# pcb1a.net
KiCad netlist of a schematic drawn in EAGLE
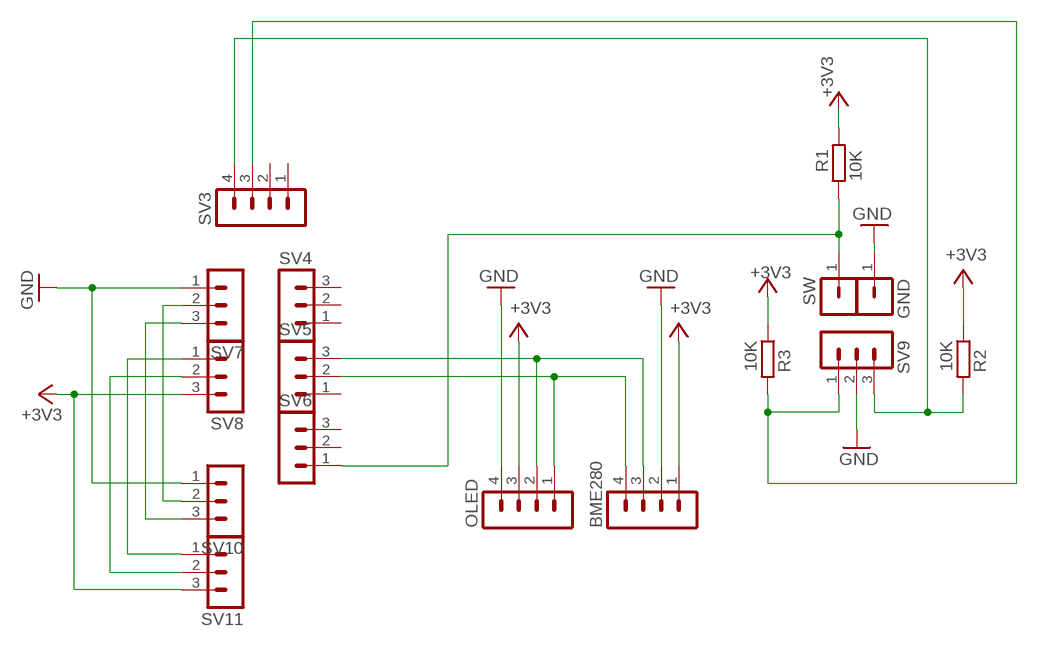
[diagram p0: schematic, sheet 1]

(export (version "E")
  (design (tool "Eeschema 10.0.6"))
  (components
    (comp (ref "BME280")
      (value "PINHEAD-MA04-1")
      (footprint "eagle-import:PINHEAD-MA04-1")
      (libsource (lib "eagle-import") (part "PINHEAD-MA04-1"))
    )
    (comp (ref "GND")
      (value "PINHEAD-MA01-1")
      (footprint "eagle-import:PINHEAD-MA01-1")
      (libsource (lib "eagle-import") (part "PINHEAD-MA01-1"))
    )
    (comp (ref "OLED")
      (value "PINHEAD-MA04-1")
      (footprint "eagle-import:PINHEAD-MA04-1")
      (libsource (lib "eagle-import") (part "PINHEAD-MA04-1"))
    )
    (comp (ref "R1")
      (value "10K")
      (footprint "eagle-import:0204_5")
      (libsource (lib "eagle-import") (part "R-EU_0204/5"))
    )
    (comp (ref "R2")
      (value "10K")
      (footprint "eagle-import:0204_5")
      (libsource (lib "eagle-import") (part "R-EU_0204/5"))
    )
    (comp (ref "R3")
      (value "10K")
      (footprint "eagle-import:0204_5")
      (libsource (lib "eagle-import") (part "R-EU_0204/5"))
    )
    (comp (ref "SV3")
      (value "PINHEAD-MA04-1")
      (footprint "eagle-import:PINHEAD-MA04-1")
      (libsource (lib "eagle-import") (part "PINHEAD-MA04-1"))
    )
    (comp (ref "SV4")
      (value "PINHEAD-MA03-1")
      (footprint "eagle-import:PINHEAD-MA03-1")
      (libsource (lib "eagle-import") (part "PINHEAD-MA03-1"))
    )
    (comp (ref "SV5")
      (value "PINHEAD-MA03-1")
      (footprint "eagle-import:PINHEAD-MA03-1")
      (libsource (lib "eagle-import") (part "PINHEAD-MA03-1"))
    )
    (comp (ref "SV6")
      (value "PINHEAD-MA03-1")
      (footprint "eagle-import:PINHEAD-MA03-1")
      (libsource (lib "eagle-import") (part "PINHEAD-MA03-1"))
    )
    (comp (ref "SV7")
      (value "PINHEAD-MA03-1")
      (footprint "eagle-import:PINHEAD-MA03-1")
      (libsource (lib "eagle-import") (part "PINHEAD-MA03-1"))
    )
    (comp (ref "SV8")
      (value "PINHEAD-MA03-1")
      (footprint "eagle-import:PINHEAD-MA03-1")
      (libsource (lib "eagle-import") (part "PINHEAD-MA03-1"))
    )
    (comp (ref "SV9")
      (value "PINHEAD-MA03-1")
      (footprint "eagle-import:PINHEAD-MA03-1")
      (libsource (lib "eagle-import") (part "PINHEAD-MA03-1"))
    )
    (comp (ref "SV10")
      (value "PINHEAD-MA03-1")
      (footprint "eagle-import:PINHEAD-MA03-1")
      (libsource (lib "eagle-import") (part "PINHEAD-MA03-1"))
    )
    (comp (ref "SV11")
      (value "PINHEAD-MA03-1")
      (footprint "eagle-import:PINHEAD-MA03-1")
      (libsource (lib "eagle-import") (part "PINHEAD-MA03-1"))
    )
    (comp (ref "SW")
      (value "PINHEAD-MA01-1")
      (footprint "eagle-import:PINHEAD-MA01-1")
      (libsource (lib "eagle-import") (part "PINHEAD-MA01-1"))
    )
  )
  (nets
    (net (code "1") (name "+3V3") (class "Default")
      (node (ref "BME280") (pin "1") (pinfunction "1_1") (pintype "passive"))
      (node (ref "OLED") (pin "3") (pinfunction "3_3") (pintype "passive"))
      (node (ref "R1") (pin "2") (pinfunction "2_2") (pintype "passive"))
      (node (ref "R2") (pin "1") (pinfunction "1_1") (pintype "passive"))
      (node (ref "R3") (pin "1") (pinfunction "1_1") (pintype "passive"))
      (node (ref "SV11") (pin "3") (pinfunction "3_3") (pintype "passive"))
      (node (ref "SV8") (pin "3") (pinfunction "3_3") (pintype "passive"))
    )
    (net (code "2") (name "GND") (class "Default")
      (node (ref "BME280") (pin "2") (pinfunction "2_2") (pintype "passive"))
      (node (ref "GND") (pin "1") (pinfunction "1_1") (pintype "passive"))
      (node (ref "OLED") (pin "4") (pinfunction "4_4") (pintype "passive"))
      (node (ref "SV10") (pin "1") (pinfunction "1_1") (pintype "passive"))
      (node (ref "SV7") (pin "1") (pinfunction "1_1") (pintype "passive"))
      (node (ref "SV9") (pin "2") (pinfunction "2_2") (pintype "passive"))
    )
    (net (code "3") (name "Net-(BME280-Pad3)") (class "Default")
      (node (ref "BME280") (pin "3") (pinfunction "3_3") (pintype "passive"))
      (node (ref "OLED") (pin "2") (pinfunction "2_2") (pintype "passive"))
      (node (ref "SV5") (pin "3") (pinfunction "3_3") (pintype "passive"))
    )
    (net (code "4") (name "Net-(BME280-Pad4)") (class "Default")
      (node (ref "BME280") (pin "4") (pinfunction "4_4") (pintype "passive"))
      (node (ref "OLED") (pin "1") (pinfunction "1_1") (pintype "passive"))
      (node (ref "SV5") (pin "2") (pinfunction "2_2") (pintype "passive"))
    )
    (net (code "5") (name "Net-(R1-Pad1)") (class "Default")
      (node (ref "R1") (pin "1") (pinfunction "1_1") (pintype "passive"))
      (node (ref "SV6") (pin "1") (pinfunction "1_1") (pintype "passive"))
      (node (ref "SW") (pin "1") (pinfunction "1_1") (pintype "passive"))
    )
    (net (code "6") (name "Net-(R2-Pad2)") (class "Default")
      (node (ref "R2") (pin "2") (pinfunction "2_2") (pintype "passive"))
      (node (ref "SV3") (pin "4") (pinfunction "4_4") (pintype "passive"))
      (node (ref "SV9") (pin "3") (pinfunction "3_3") (pintype "passive"))
    )
    (net (code "7") (name "Net-(R3-Pad2)") (class "Default")
      (node (ref "R3") (pin "2") (pinfunction "2_2") (pintype "passive"))
      (node (ref "SV3") (pin "3") (pinfunction "3_3") (pintype "passive"))
      (node (ref "SV9") (pin "1") (pinfunction "1_1") (pintype "passive"))
    )
    (net (code "8") (name "Net-(SV10-Pad2)") (class "Default")
      (node (ref "SV10") (pin "2") (pinfunction "2_2") (pintype "passive"))
      (node (ref "SV7") (pin "2") (pinfunction "2_2") (pintype "passive"))
    )
    (net (code "9") (name "Net-(SV10-Pad3)") (class "Default")
      (node (ref "SV10") (pin "3") (pinfunction "3_3") (pintype "passive"))
      (node (ref "SV7") (pin "3") (pinfunction "3_3") (pintype "passive"))
    )
    (net (code "10") (name "Net-(SV11-Pad1)") (class "Default")
      (node (ref "SV11") (pin "1") (pinfunction "1_1") (pintype "passive"))
      (node (ref "SV8") (pin "1") (pinfunction "1_1") (pintype "passive"))
    )
    (net (code "11") (name "Net-(SV11-Pad2)") (class "Default")
      (node (ref "SV11") (pin "2") (pinfunction "2_2") (pintype "passive"))
      (node (ref "SV8") (pin "2") (pinfunction "2_2") (pintype "passive"))
    )
    (net (code "12") (name "unconnected-(SV3-Pad1)") (class "Default")
      (node (ref "SV3") (pin "1") (pinfunction "1_1") (pintype "passive"))
    )
    (net (code "13") (name "unconnected-(SV3-Pad2)") (class "Default")
      (node (ref "SV3") (pin "2") (pinfunction "2_2") (pintype "passive"))
    )
    (net (code "14") (name "unconnected-(SV4-Pad1)") (class "Default")
      (node (ref "SV4") (pin "1") (pinfunction "1_1") (pintype "passive"))
    )
    (net (code "15") (name "unconnected-(SV4-Pad2)") (class "Default")
      (node (ref "SV4") (pin "2") (pinfunction "2_2") (pintype "passive"))
    )
    (net (code "16") (name "unconnected-(SV4-Pad3)") (class "Default")
      (node (ref "SV4") (pin "3") (pinfunction "3_3") (pintype "passive"))
    )
    (net (code "17") (name "unconnected-(SV5-Pad1)") (class "Default")
      (node (ref "SV5") (pin "1") (pinfunction "1_1") (pintype "passive"))
    )
    (net (code "18") (name "unconnected-(SV6-Pad2)") (class "Default")
      (node (ref "SV6") (pin "2") (pinfunction "2_2") (pintype "passive"))
    )
    (net (code "19") (name "unconnected-(SV6-Pad3)") (class "Default")
      (node (ref "SV6") (pin "3") (pinfunction "3_3") (pintype "passive"))
    )
  )
)
